# trico_embed01_atmpt02.net
KiCad netlist of a schematic drawn in EAGLE
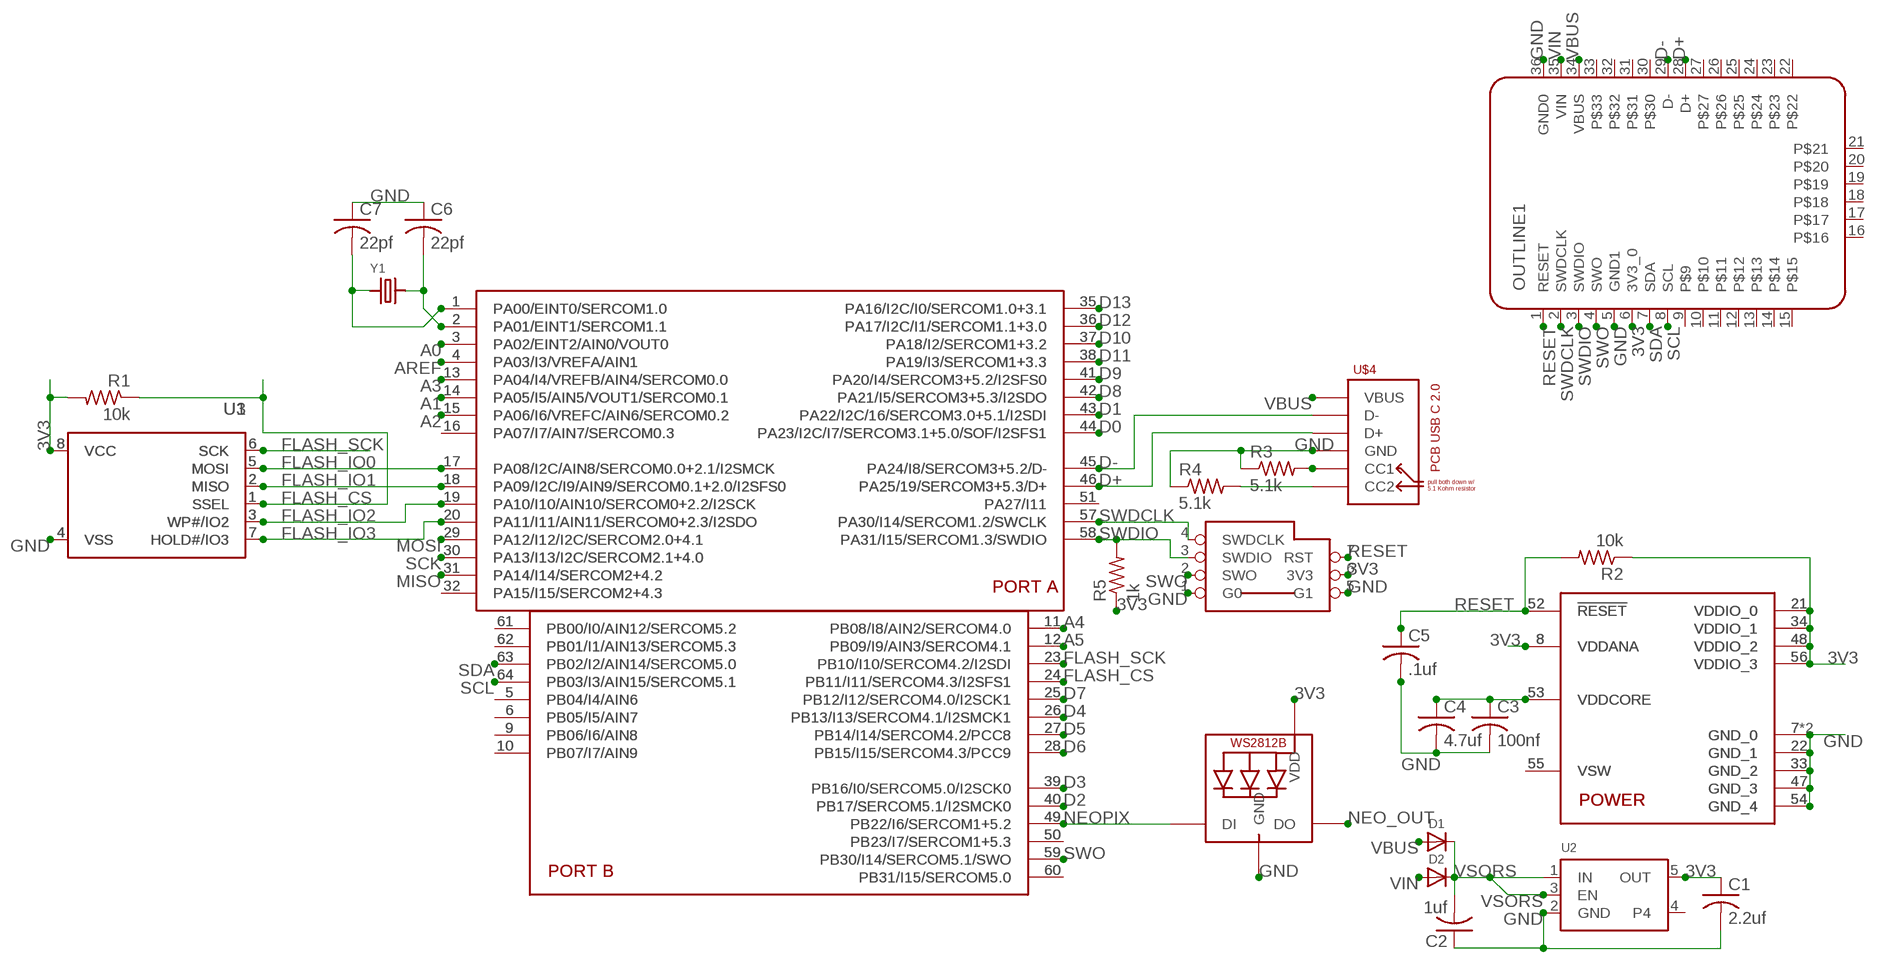
[diagram p0: schematic, sheet 1]

(export (version "E")
  (design (tool "Eeschema 10.0.6"))
  (components
    (comp (ref "C1")
      (value "2.2uf")
      (footprint "eagle-import:TG-C0805MP")
      (libsource (lib "eagle-import") (part "C-TG"))
    )
    (comp (ref "C2")
      (value "1uf")
      (footprint "eagle-import:TG-C0805MP")
      (libsource (lib "eagle-import") (part "C-TG"))
    )
    (comp (ref "C3")
      (value "100nf")
      (footprint "eagle-import:TG-C0805MP")
      (libsource (lib "eagle-import") (part "C-TG"))
    )
    (comp (ref "C4")
      (value "4.7uf")
      (footprint "eagle-import:TG-C0805MP")
      (libsource (lib "eagle-import") (part "C-TG"))
    )
    (comp (ref "C5")
      (value ".1uf")
      (footprint "eagle-import:TG-C0805MP")
      (libsource (lib "eagle-import") (part "C-TG"))
    )
    (comp (ref "C6")
      (value "22pf")
      (footprint "eagle-import:TG-C0805MP")
      (libsource (lib "eagle-import") (part "C-TG"))
    )
    (comp (ref "C7")
      (value "22pf")
      (footprint "eagle-import:TG-C0805MP")
      (libsource (lib "eagle-import") (part "C-TG"))
    )
    (comp (ref "D1")
      (value "DIODESOD-123")
      (footprint "eagle-import:SOD-123")
      (libsource (lib "eagle-import") (part "DIODESOD-123"))
    )
    (comp (ref "D2")
      (value "DIODESOD-123")
      (footprint "eagle-import:SOD-123")
      (libsource (lib "eagle-import") (part "DIODESOD-123"))
    )
    (comp (ref "LED1")
      (value "LED-NEO-WS2812B3535")
      (footprint "eagle-import:LED3535")
      (libsource (lib "eagle-import") (part "LED-NEO-WS2812B3535"))
    )
    (comp (ref "OUTLINE1")
      (value "TRIOC_DEV_36_EMBED_01BREAK_TPLC")
      (footprint "eagle-import:TRICO_DEV_01_BRK_TPLC_HYBRID")
      (libsource (lib "eagle-import") (part "TRIOC_DEV_36_EMBED_01BREAK_TPLC"))
    )
    (comp (ref "R1")
      (value "10k")
      (footprint "eagle-import:TG-R0805")
      (libsource (lib "eagle-import") (part "R_TG"))
    )
    (comp (ref "R2")
      (value "10k")
      (footprint "eagle-import:TG-R0805")
      (libsource (lib "eagle-import") (part "R_TG"))
    )
    (comp (ref "R3")
      (value "5.1k")
      (footprint "eagle-import:TG-R0805")
      (libsource (lib "eagle-import") (part "0TG-Lib v01.4_R_TG"))
    )
    (comp (ref "R4")
      (value "5.1k")
      (footprint "eagle-import:TG-R0805")
      (libsource (lib "eagle-import") (part "0TG-Lib v01.4_R_TG"))
    )
    (comp (ref "R5")
      (value "1k")
      (footprint "eagle-import:TG-R0805")
      (libsource (lib "eagle-import") (part "R_TG"))
    )
    (comp (ref "U$1")
      (value "MCU-ATSAMD51J-ADATQFP")
      (footprint "eagle-import:QFP50P1200X1200X120-64N")
      (libsource (lib "eagle-import") (part "MCU-ATSAMD51J-ADATQFP"))
    )
    (comp (ref "U$2")
      (value "MCU-ATSAMD51J-ADAADA")
      (footprint "eagle-import:MICROBUILDER_PQFN64-1")
      (libsource (lib "eagle-import") (part "0TG-Lib v01.4_MCU-ATSAMD51J-ADAADA"))
    )
    (comp (ref "U$3")
      (value "SWD_POGO")
      (footprint "eagle-import:SWD_POGO")
      (libsource (lib "eagle-import") (part "SWD_POGO"))
    )
    (comp (ref "U$4")
      (value "USB-C-PCB-USB-2.0-TYPE-CDS_2")
      (footprint "eagle-import:USB_TYPE_C_DS_2")
      (libsource (lib "eagle-import") (part "USB-C-PCB-USB-2.0-TYPE-CDS_2"))
    )
    (comp (ref "U1")
      (value "FLASH-SPI-SOIC8")
      (footprint "eagle-import:SOIC8_150MIL")
      (libsource (lib "eagle-import") (part "FLASH-SPI-SOIC8"))
    )
    (comp (ref "U2")
      (value "VREG_STD_MIN_SOT23-5")
      (footprint "eagle-import:SOT23-5")
      (libsource (lib "eagle-import") (part "VREG_STD_MIN_SOT23-5"))
    )
    (comp (ref "U3")
      (value "FLASH-SPI-SOIC8208MIL")
      (footprint "eagle-import:SOIC8_208MIL")
      (libsource (lib "eagle-import") (part "FLASH-SPI-SOIC8208MIL"))
    )
    (comp (ref "Y1")
      (value "XTAL_ADA4.9X1.8")
      (footprint "eagle-import:MICROBUILDER_CRYSTAL_4.9X1.8")
      (libsource (lib "eagle-import") (part "XTAL_ADA4.9X1.8"))
    )
  )
  (nets
    (net (code "1") (name "/3V3") (class "Default")
      (node (ref "C1") (pin "1") (pinfunction "1_1") (pintype "passive"))
      (node (ref "LED1") (pin "2") (pinfunction "VDD_2") (pintype "power_in"))
      (node (ref "OUTLINE1") (pin "6") (pinfunction "3V3_0_6") (pintype "bidirectional"))
      (node (ref "R1") (pin "2") (pinfunction "2_2") (pintype "passive"))
      (node (ref "R2") (pin "1") (pinfunction "1_1") (pintype "passive"))
      (node (ref "R5") (pin "1") (pinfunction "1_1") (pintype "passive"))
      (node (ref "U$1") (pin "21") (pinfunction "VDDIO_0_21") (pintype "bidirectional"))
      (node (ref "U$1") (pin "34") (pinfunction "VDDIO_1_34") (pintype "bidirectional"))
      (node (ref "U$1") (pin "48") (pinfunction "VDDIO_2_48") (pintype "bidirectional"))
      (node (ref "U$1") (pin "56") (pinfunction "VDDIO_3_56") (pintype "bidirectional"))
      (node (ref "U$1") (pin "8") (pinfunction "VDDANA_8") (pintype "bidirectional"))
      (node (ref "U$2") (pin "21") (pinfunction "VDDIO_0_21") (pintype "bidirectional"))
      (node (ref "U$2") (pin "34") (pinfunction "VDDIO_1_34") (pintype "bidirectional"))
      (node (ref "U$2") (pin "48") (pinfunction "VDDIO_2_48") (pintype "bidirectional"))
      (node (ref "U$2") (pin "56") (pinfunction "VDDIO_3_56") (pintype "bidirectional"))
      (node (ref "U$2") (pin "8") (pinfunction "VDDANA_8") (pintype "bidirectional"))
      (node (ref "U$3") (pin "6") (pinfunction "3V3_6") (pintype "bidirectional"))
      (node (ref "U1") (pin "8") (pinfunction "VCC_8") (pintype "bidirectional"))
      (node (ref "U2") (pin "5") (pinfunction "OUT_5") (pintype "power_in"))
      (node (ref "U3") (pin "8") (pinfunction "VCC_8") (pintype "bidirectional"))
    )
    (net (code "2") (name "/A0") (class "Default")
      (node (ref "U$1") (pin "3") (pinfunction "PA02/EINT2/AIN0/VOUT0_3") (pintype "bidirectional"))
      (node (ref "U$2") (pin "3") (pinfunction "PA02/EINT2/AIN0/VOUT0_3") (pintype "bidirectional"))
    )
    (net (code "3") (name "/A1") (class "Default")
      (node (ref "U$1") (pin "14") (pinfunction "PA05/I5/AIN5/VOUT1/SERCOM0.1_14") (pintype "bidirectional"))
      (node (ref "U$2") (pin "14") (pinfunction "PA05/I5/AIN5/VOUT1/SERCOM0.1_14") (pintype "bidirectional"))
    )
    (net (code "4") (name "/A2") (class "Default")
      (node (ref "U$1") (pin "15") (pinfunction "PA06/I6/VREFC/AIN6/SERCOM0.2_15") (pintype "bidirectional"))
      (node (ref "U$2") (pin "15") (pinfunction "PA06/I6/VREFC/AIN6/SERCOM0.2_15") (pintype "bidirectional"))
    )
    (net (code "5") (name "/A3") (class "Default")
      (node (ref "U$1") (pin "13") (pinfunction "PA04/I4/VREFB/AIN4/SERCOM0.0_13") (pintype "bidirectional"))
      (node (ref "U$2") (pin "13") (pinfunction "PA04/I4/VREFB/AIN4/SERCOM0.0_13") (pintype "bidirectional"))
    )
    (net (code "6") (name "/A4") (class "Default")
      (node (ref "U$1") (pin "11") (pinfunction "PB08/I8/AIN2/SERCOM4.0_11") (pintype "bidirectional"))
      (node (ref "U$2") (pin "11") (pinfunction "PB08/I8/AIN2/SERCOM4.0_11") (pintype "bidirectional"))
    )
    (net (code "7") (name "/A5") (class "Default")
      (node (ref "U$1") (pin "12") (pinfunction "PB09/I9/AIN3/SERCOM4.1_12") (pintype "bidirectional"))
      (node (ref "U$2") (pin "12") (pinfunction "PB09/I9/AIN3/SERCOM4.1_12") (pintype "bidirectional"))
    )
    (net (code "8") (name "/AREF") (class "Default")
      (node (ref "U$1") (pin "4") (pinfunction "PA03/I3/VREFA/AIN1_4") (pintype "bidirectional"))
      (node (ref "U$2") (pin "4") (pinfunction "PA03/I3/VREFA/AIN1_4") (pintype "bidirectional"))
    )
    (net (code "9") (name "/D+") (class "Default")
      (node (ref "OUTLINE1") (pin "28") (pinfunction "D+_28") (pintype "bidirectional"))
      (node (ref "U$1") (pin "46") (pinfunction "PA25/19/SERCOM3+5.3/D+_46") (pintype "bidirectional"))
      (node (ref "U$2") (pin "46") (pinfunction "PA25/19/SERCOM3+5.3/D+_46") (pintype "bidirectional"))
      (node (ref "U$4") (pin "A6") (pinfunction "D+_A6") (pintype "bidirectional"))
      (node (ref "U$4") (pin "B6") (pinfunction "D+_B6") (pintype "bidirectional"))
    )
    (net (code "10") (name "/D-") (class "Default")
      (node (ref "OUTLINE1") (pin "29") (pinfunction "D-_29") (pintype "bidirectional"))
      (node (ref "U$1") (pin "45") (pinfunction "PA24/I8/SERCOM3+5.2/D-_45") (pintype "bidirectional"))
      (node (ref "U$2") (pin "45") (pinfunction "PA24/I8/SERCOM3+5.2/D-_45") (pintype "bidirectional"))
      (node (ref "U$4") (pin "A7") (pinfunction "D-_A7") (pintype "bidirectional"))
      (node (ref "U$4") (pin "B7") (pinfunction "D-_B7") (pintype "bidirectional"))
    )
    (net (code "11") (name "/D0") (class "Default")
      (node (ref "U$1") (pin "44") (pinfunction "PA23/I2C/I7/SERCOM3.1+5.0/SOF/I2SFS1_44") (pintype "bidirectional"))
      (node (ref "U$2") (pin "44") (pinfunction "PA23/I2C/I7/SERCOM3.1+5.0/SOF/I2SFS1_44") (pintype "bidirectional"))
    )
    (net (code "12") (name "/D1") (class "Default")
      (node (ref "U$1") (pin "43") (pinfunction "PA22/I2C/16/SERCOM3.0+5.1/I2SDI_43") (pintype "bidirectional"))
      (node (ref "U$2") (pin "43") (pinfunction "PA22/I2C/16/SERCOM3.0+5.1/I2SDI_43") (pintype "bidirectional"))
    )
    (net (code "13") (name "/D2") (class "Default")
      (node (ref "U$1") (pin "40") (pinfunction "PB17/SERCOM5.1/I2SMCK0_40") (pintype "bidirectional"))
      (node (ref "U$2") (pin "40") (pinfunction "PB17/SERCOM5.1/I2SMCK0_40") (pintype "bidirectional"))
    )
    (net (code "14") (name "/D3") (class "Default")
      (node (ref "U$1") (pin "39") (pinfunction "PB16/I0/SERCOM5.0/I2SCK0_39") (pintype "bidirectional"))
      (node (ref "U$2") (pin "39") (pinfunction "PB16/I0/SERCOM5.0/I2SCK0_39") (pintype "bidirectional"))
    )
    (net (code "15") (name "/D4") (class "Default")
      (node (ref "U$1") (pin "26") (pinfunction "PB13/I13/SERCOM4.1/I2SMCK1_26") (pintype "bidirectional"))
      (node (ref "U$2") (pin "26") (pinfunction "PB13/I13/SERCOM4.1/I2SMCK1_26") (pintype "bidirectional"))
    )
    (net (code "16") (name "/D5") (class "Default")
      (node (ref "U$1") (pin "27") (pinfunction "PB14/I14/SERCOM4.2/PCC8_27") (pintype "bidirectional"))
      (node (ref "U$2") (pin "27") (pinfunction "PB14/I14/SERCOM4.2/PCC8_27") (pintype "bidirectional"))
    )
    (net (code "17") (name "/D6") (class "Default")
      (node (ref "U$1") (pin "28") (pinfunction "PB15/I15/SERCOM4.3/PCC9_28") (pintype "bidirectional"))
      (node (ref "U$2") (pin "28") (pinfunction "PB15/I15/SERCOM4.3/PCC9_28") (pintype "bidirectional"))
    )
    (net (code "18") (name "/D7") (class "Default")
      (node (ref "U$1") (pin "25") (pinfunction "PB12/I12/SERCOM4.0/I2SCK1_25") (pintype "bidirectional"))
      (node (ref "U$2") (pin "25") (pinfunction "PB12/I12/SERCOM4.0/I2SCK1_25") (pintype "bidirectional"))
    )
    (net (code "19") (name "/D8") (class "Default")
      (node (ref "U$1") (pin "42") (pinfunction "PA21/I5/SERCOM3+5.3/I2SDO_42") (pintype "bidirectional"))
      (node (ref "U$2") (pin "42") (pinfunction "PA21/I5/SERCOM3+5.3/I2SDO_42") (pintype "bidirectional"))
    )
    (net (code "20") (name "/D9") (class "Default")
      (node (ref "U$1") (pin "41") (pinfunction "PA20/I4/SERCOM3+5.2/I2SFS0_41") (pintype "bidirectional"))
      (node (ref "U$2") (pin "41") (pinfunction "PA20/I4/SERCOM3+5.2/I2SFS0_41") (pintype "bidirectional"))
    )
    (net (code "21") (name "/D10") (class "Default")
      (node (ref "U$1") (pin "37") (pinfunction "PA18/I2/SERCOM1+3.2_37") (pintype "bidirectional"))
      (node (ref "U$2") (pin "37") (pinfunction "PA18/I2/SERCOM1+3.2_37") (pintype "bidirectional"))
    )
    (net (code "22") (name "/D11") (class "Default")
      (node (ref "U$1") (pin "38") (pinfunction "PA19/I3/SERCOM1+3.3_38") (pintype "bidirectional"))
      (node (ref "U$2") (pin "38") (pinfunction "PA19/I3/SERCOM1+3.3_38") (pintype "bidirectional"))
    )
    (net (code "23") (name "/D12") (class "Default")
      (node (ref "U$1") (pin "36") (pinfunction "PA17/I2C/I1/SERCOM1.1+3.0_36") (pintype "bidirectional"))
      (node (ref "U$2") (pin "36") (pinfunction "PA17/I2C/I1/SERCOM1.1+3.0_36") (pintype "bidirectional"))
    )
    (net (code "24") (name "/D13") (class "Default")
      (node (ref "U$1") (pin "35") (pinfunction "PA16/I2C/I0/SERCOM1.0+3.1_35") (pintype "bidirectional"))
      (node (ref "U$2") (pin "35") (pinfunction "PA16/I2C/I0/SERCOM1.0+3.1_35") (pintype "bidirectional"))
    )
    (net (code "25") (name "/FLASH_CS") (class "Default")
      (node (ref "R1") (pin "1") (pinfunction "1_1") (pintype "passive"))
      (node (ref "U$1") (pin "24") (pinfunction "PB11/I11/SERCOM4.3/I2SFS1_24") (pintype "bidirectional"))
      (node (ref "U$2") (pin "24") (pinfunction "PB11/I11/SERCOM4.3/I2SFS1_24") (pintype "bidirectional"))
      (node (ref "U1") (pin "1") (pinfunction "SSEL_1") (pintype "bidirectional"))
      (node (ref "U3") (pin "1") (pinfunction "SSEL_1") (pintype "bidirectional"))
    )
    (net (code "26") (name "/FLASH_IO0") (class "Default")
      (node (ref "U$1") (pin "17") (pinfunction "PA08/I2C/AIN8/SERCOM0.0+2.1/I2SMCK_17") (pintype "bidirectional"))
      (node (ref "U$2") (pin "17") (pinfunction "PA08/I2C/AIN8/SERCOM0.0+2.1/I2SMCK_17") (pintype "bidirectional"))
      (node (ref "U1") (pin "5") (pinfunction "MOSI_5") (pintype "bidirectional"))
      (node (ref "U3") (pin "5") (pinfunction "MOSI_5") (pintype "bidirectional"))
    )
    (net (code "27") (name "/FLASH_IO1") (class "Default")
      (node (ref "U$1") (pin "18") (pinfunction "PA09/I2C/I9/AIN9/SERCOM0.1+2.0/I2SFS0_18") (pintype "bidirectional"))
      (node (ref "U$2") (pin "18") (pinfunction "PA09/I2C/I9/AIN9/SERCOM0.1+2.0/I2SFS0_18") (pintype "bidirectional"))
      (node (ref "U1") (pin "2") (pinfunction "MISO_2") (pintype "bidirectional"))
      (node (ref "U3") (pin "2") (pinfunction "MISO_2") (pintype "bidirectional"))
    )
    (net (code "28") (name "/FLASH_IO2") (class "Default")
      (node (ref "U$1") (pin "19") (pinfunction "PA10/I10/AIN10/SERCOM0+2.2/I2SCK_19") (pintype "bidirectional"))
      (node (ref "U$2") (pin "19") (pinfunction "PA10/I10/AIN10/SERCOM0+2.2/I2SCK_19") (pintype "bidirectional"))
      (node (ref "U1") (pin "3") (pinfunction "WP#/IO2_3") (pintype "bidirectional"))
      (node (ref "U3") (pin "3") (pinfunction "WP#/IO2_3") (pintype "bidirectional"))
    )
    (net (code "29") (name "/FLASH_IO3") (class "Default")
      (node (ref "U$1") (pin "20") (pinfunction "PA11/I11/AIN11/SERCOM0+2.3/I2SDO_20") (pintype "bidirectional"))
      (node (ref "U$2") (pin "20") (pinfunction "PA11/I11/AIN11/SERCOM0+2.3/I2SDO_20") (pintype "bidirectional"))
      (node (ref "U1") (pin "7") (pinfunction "HOLD#/IO3_7") (pintype "bidirectional"))
      (node (ref "U3") (pin "7") (pinfunction "HOLD#/IO3_7") (pintype "bidirectional"))
    )
    (net (code "30") (name "/FLASH_SCK") (class "Default")
      (node (ref "U$1") (pin "23") (pinfunction "PB10/I10/SERCOM4.2/I2SDI_23") (pintype "bidirectional"))
      (node (ref "U$2") (pin "23") (pinfunction "PB10/I10/SERCOM4.2/I2SDI_23") (pintype "bidirectional"))
      (node (ref "U1") (pin "6") (pinfunction "SCK_6") (pintype "bidirectional"))
      (node (ref "U3") (pin "6") (pinfunction "SCK_6") (pintype "bidirectional"))
    )
    (net (code "31") (name "/GND") (class "Default")
      (node (ref "C1") (pin "2") (pinfunction "2_2") (pintype "passive"))
      (node (ref "C2") (pin "1") (pinfunction "1_1") (pintype "passive"))
      (node (ref "C3") (pin "2") (pinfunction "2_2") (pintype "passive"))
      (node (ref "C4") (pin "2") (pinfunction "2_2") (pintype "passive"))
      (node (ref "C5") (pin "2") (pinfunction "2_2") (pintype "passive"))
      (node (ref "C6") (pin "1") (pinfunction "1_1") (pintype "passive"))
      (node (ref "C7") (pin "1") (pinfunction "1_1") (pintype "passive"))
      (node (ref "LED1") (pin "4") (pinfunction "GND_4") (pintype "power_in"))
      (node (ref "OUTLINE1") (pin "36") (pinfunction "GND0_36") (pintype "bidirectional"))
      (node (ref "OUTLINE1") (pin "5") (pinfunction "GND1_5") (pintype "bidirectional"))
      (node (ref "R3") (pin "1") (pinfunction "1_1") (pintype "passive"))
      (node (ref "R4") (pin "1") (pinfunction "1_1") (pintype "passive"))
      (node (ref "U$1") (pin "22") (pinfunction "GND_1_22") (pintype "bidirectional"))
      (node (ref "U$1") (pin "33") (pinfunction "GND_2_33") (pintype "bidirectional"))
      (node (ref "U$1") (pin "47") (pinfunction "GND_3_47") (pintype "bidirectional"))
      (node (ref "U$1") (pin "54") (pinfunction "GND_4_54") (pintype "bidirectional"))
      (node (ref "U$1") (pin "7") (pinfunction "GND_0_7") (pintype "bidirectional"))
      (node (ref "U$2") (pin "22") (pinfunction "GND_1_22") (pintype "bidirectional"))
      (node (ref "U$2") (pin "33") (pinfunction "GND_2_33") (pintype "bidirectional"))
      (node (ref "U$2") (pin "47") (pinfunction "GND_3_47") (pintype "bidirectional"))
      (node (ref "U$2") (pin "54") (pinfunction "GND_4_54") (pintype "bidirectional"))
      (node (ref "U$2") (pin "7") (pinfunction "GND_0_7") (pintype "bidirectional"))
      (node (ref "U$2") (pin "EXP") (pinfunction "GND_0_EXP") (pintype "bidirectional"))
      (node (ref "U$3") (pin "1") (pinfunction "G0_1") (pintype "bidirectional"))
      (node (ref "U$3") (pin "5") (pinfunction "G1_5") (pintype "bidirectional"))
      (node (ref "U$4") (pin "A1") (pinfunction "GND_A1") (pintype "bidirectional"))
      (node (ref "U$4") (pin "A12") (pinfunction "GND_A12") (pintype "bidirectional"))
      (node (ref "U$4") (pin "B1") (pinfunction "GND_B1") (pintype "bidirectional"))
      (node (ref "U$4") (pin "B12") (pinfunction "GND_B12") (pintype "bidirectional"))
      (node (ref "U1") (pin "4") (pinfunction "VSS_4") (pintype "bidirectional"))
      (node (ref "U2") (pin "2") (pinfunction "GND_2") (pintype "power_in"))
      (node (ref "U3") (pin "4") (pinfunction "VSS_4") (pintype "bidirectional"))
    )
    (net (code "32") (name "/MISO") (class "Default")
      (node (ref "U$1") (pin "31") (pinfunction "PA14/I14/SERCOM2+4.2_31") (pintype "bidirectional"))
      (node (ref "U$2") (pin "31") (pinfunction "PA14/I14/SERCOM2+4.2_31") (pintype "bidirectional"))
    )
    (net (code "33") (name "/MOSI") (class "Default")
      (node (ref "U$1") (pin "29") (pinfunction "PA12/I12/I2C/SERCOM2.0+4.1_29") (pintype "bidirectional"))
      (node (ref "U$2") (pin "29") (pinfunction "PA12/I12/I2C/SERCOM2.0+4.1_29") (pintype "bidirectional"))
    )
    (net (code "34") (name "/NEOPIX") (class "Default")
      (node (ref "LED1") (pin "1") (pinfunction "DI_1") (pintype "input"))
      (node (ref "U$1") (pin "49") (pinfunction "PB22/I6/SERCOM1+5.2_49") (pintype "bidirectional"))
      (node (ref "U$2") (pin "49") (pinfunction "PB22/I6/SERCOM1+5.2_49") (pintype "bidirectional"))
    )
    (net (code "35") (name "/NEO_OUT") (class "Default")
      (node (ref "LED1") (pin "3") (pinfunction "DO_3") (pintype "output"))
    )
    (net (code "36") (name "/RESET") (class "Default")
      (node (ref "C5") (pin "1") (pinfunction "1_1") (pintype "passive"))
      (node (ref "OUTLINE1") (pin "1") (pinfunction "RESET_1") (pintype "bidirectional"))
      (node (ref "R2") (pin "2") (pinfunction "2_2") (pintype "passive"))
      (node (ref "U$1") (pin "52") (pinfunction "~{RESET}_52") (pintype "bidirectional"))
      (node (ref "U$2") (pin "52") (pinfunction "~{RESET}_52") (pintype "bidirectional"))
      (node (ref "U$3") (pin "7") (pinfunction "RST_7") (pintype "bidirectional"))
    )
    (net (code "37") (name "/SCK") (class "Default")
      (node (ref "U$1") (pin "30") (pinfunction "PA13/I13/I2C/SERCOM2.1+4.0_30") (pintype "bidirectional"))
      (node (ref "U$2") (pin "30") (pinfunction "PA13/I13/I2C/SERCOM2.1+4.0_30") (pintype "bidirectional"))
    )
    (net (code "38") (name "/SCL") (class "Default")
      (node (ref "OUTLINE1") (pin "8") (pinfunction "SCL_8") (pintype "bidirectional"))
      (node (ref "U$1") (pin "64") (pinfunction "PB03/I3/AIN15/SERCOM5.1_64") (pintype "bidirectional"))
      (node (ref "U$2") (pin "64") (pinfunction "PB03/I3/AIN15/SERCOM5.1_64") (pintype "bidirectional"))
    )
    (net (code "39") (name "/SDA") (class "Default")
      (node (ref "OUTLINE1") (pin "7") (pinfunction "SDA_7") (pintype "bidirectional"))
      (node (ref "U$1") (pin "63") (pinfunction "PB02/I2/AIN14/SERCOM5.0_63") (pintype "bidirectional"))
      (node (ref "U$2") (pin "63") (pinfunction "PB02/I2/AIN14/SERCOM5.0_63") (pintype "bidirectional"))
    )
    (net (code "40") (name "/SWDCLK") (class "Default")
      (node (ref "OUTLINE1") (pin "2") (pinfunction "SWDCLK_2") (pintype "bidirectional"))
      (node (ref "U$1") (pin "57") (pinfunction "PA30/I14/SERCOM1.2/SWCLK_57") (pintype "bidirectional"))
      (node (ref "U$2") (pin "57") (pinfunction "PA30/I14/SERCOM1.2/SWCLK_57") (pintype "bidirectional"))
      (node (ref "U$3") (pin "4") (pinfunction "SWDCLK_4") (pintype "bidirectional"))
    )
    (net (code "41") (name "/SWDIO") (class "Default")
      (node (ref "OUTLINE1") (pin "3") (pinfunction "SWDIO_3") (pintype "bidirectional"))
      (node (ref "R5") (pin "2") (pinfunction "2_2") (pintype "passive"))
      (node (ref "U$1") (pin "58") (pinfunction "PA31/I15/SERCOM1.3/SWDIO_58") (pintype "bidirectional"))
      (node (ref "U$2") (pin "58") (pinfunction "PA31/I15/SERCOM1.3/SWDIO_58") (pintype "bidirectional"))
      (node (ref "U$3") (pin "3") (pinfunction "SWDIO_3") (pintype "bidirectional"))
    )
    (net (code "42") (name "/SWO") (class "Default")
      (node (ref "OUTLINE1") (pin "4") (pinfunction "SWO_4") (pintype "bidirectional"))
      (node (ref "U$1") (pin "59") (pinfunction "PB30/I14/SERCOM5.1/SWO_59") (pintype "bidirectional"))
      (node (ref "U$2") (pin "59") (pinfunction "PB30/I14/SERCOM5.1/SWO_59") (pintype "bidirectional"))
      (node (ref "U$3") (pin "2") (pinfunction "SWO_2") (pintype "bidirectional"))
    )
    (net (code "43") (name "/VBUS") (class "Default")
      (node (ref "D1") (pin "A") (pinfunction "A_A") (pintype "passive"))
      (node (ref "OUTLINE1") (pin "34") (pinfunction "VBUS_34") (pintype "bidirectional"))
      (node (ref "U$4") (pin "A4") (pinfunction "VBUS_A4") (pintype "bidirectional"))
      (node (ref "U$4") (pin "A9") (pinfunction "VBUS_A9") (pintype "bidirectional"))
      (node (ref "U$4") (pin "B4") (pinfunction "VBUS_B4") (pintype "bidirectional"))
      (node (ref "U$4") (pin "B9") (pinfunction "VBUS_B9") (pintype "bidirectional"))
    )
    (net (code "44") (name "/VIN") (class "Default")
      (node (ref "D2") (pin "A") (pinfunction "A_A") (pintype "passive"))
      (node (ref "OUTLINE1") (pin "35") (pinfunction "VIN_35") (pintype "bidirectional"))
    )
    (net (code "45") (name "/VSORS") (class "Default")
      (node (ref "C2") (pin "2") (pinfunction "2_2") (pintype "passive"))
      (node (ref "D1") (pin "C") (pinfunction "C_C") (pintype "passive"))
      (node (ref "D2") (pin "C") (pinfunction "C_C") (pintype "passive"))
      (node (ref "U2") (pin "1") (pinfunction "IN_1") (pintype "power_in"))
      (node (ref "U2") (pin "3") (pinfunction "EN_3") (pintype "input"))
    )
    (net (code "46") (name "Net-(U$1A-PA00{slash}EINT0{slash}SERCOM1.0)") (class "Default")
      (node (ref "C7") (pin "2") (pinfunction "2_2") (pintype "passive"))
      (node (ref "U$1") (pin "1") (pinfunction "PA00/EINT0/SERCOM1.0_1") (pintype "bidirectional"))
      (node (ref "U$2") (pin "1") (pinfunction "PA00/EINT0/SERCOM1.0_1") (pintype "bidirectional"))
      (node (ref "Y1") (pin "1") (pinfunction "1_1") (pintype "passive"))
    )
    (net (code "47") (name "Net-(U$1A-PA01{slash}EINT1{slash}SERCOM1.1)") (class "Default")
      (node (ref "C6") (pin "2") (pinfunction "2_2") (pintype "passive"))
      (node (ref "U$1") (pin "2") (pinfunction "PA01/EINT1/SERCOM1.1_2") (pintype "bidirectional"))
      (node (ref "U$2") (pin "2") (pinfunction "PA01/EINT1/SERCOM1.1_2") (pintype "bidirectional"))
      (node (ref "Y1") (pin "2") (pinfunction "2_2") (pintype "passive"))
    )
    (net (code "48") (name "Net-(U$1A-PA07{slash}I7{slash}AIN7{slash}SERCOM0.3)") (class "Default")
      (node (ref "U$1") (pin "16") (pinfunction "PA07/I7/AIN7/SERCOM0.3_16") (pintype "bidirectional"))
      (node (ref "U$2") (pin "16") (pinfunction "PA07/I7/AIN7/SERCOM0.3_16") (pintype "bidirectional"))
    )
    (net (code "49") (name "Net-(U$1A-PA15{slash}I15{slash}SERCOM2+4.3)") (class "Default")
      (node (ref "U$1") (pin "32") (pinfunction "PA15/I15/SERCOM2+4.3_32") (pintype "bidirectional"))
      (node (ref "U$2") (pin "32") (pinfunction "PA15/I15/SERCOM2+4.3_32") (pintype "bidirectional"))
    )
    (net (code "50") (name "Net-(U$1A-PA27{slash}I11)") (class "Default")
      (node (ref "U$1") (pin "51") (pinfunction "PA27/I11_51") (pintype "bidirectional"))
      (node (ref "U$2") (pin "51") (pinfunction "PA27/I11_51") (pintype "bidirectional"))
    )
    (net (code "51") (name "Net-(U$1B-PB00{slash}I0{slash}AIN12{slash}SERCOM5.2)") (class "Default")
      (node (ref "U$1") (pin "61") (pinfunction "PB00/I0/AIN12/SERCOM5.2_61") (pintype "bidirectional"))
      (node (ref "U$2") (pin "61") (pinfunction "PB00/I0/AIN12/SERCOM5.2_61") (pintype "bidirectional"))
    )
    (net (code "52") (name "Net-(U$1B-PB01{slash}I1{slash}AIN13{slash}SERCOM5.3)") (class "Default")
      (node (ref "U$1") (pin "62") (pinfunction "PB01/I1/AIN13/SERCOM5.3_62") (pintype "bidirectional"))
      (node (ref "U$2") (pin "62") (pinfunction "PB01/I1/AIN13/SERCOM5.3_62") (pintype "bidirectional"))
    )
    (net (code "53") (name "Net-(U$1B-PB04{slash}I4{slash}AIN6)") (class "Default")
      (node (ref "U$1") (pin "5") (pinfunction "PB04/I4/AIN6_5") (pintype "bidirectional"))
      (node (ref "U$2") (pin "5") (pinfunction "PB04/I4/AIN6_5") (pintype "bidirectional"))
    )
    (net (code "54") (name "Net-(U$1B-PB05{slash}I5{slash}AIN7)") (class "Default")
      (node (ref "U$1") (pin "6") (pinfunction "PB05/I5/AIN7_6") (pintype "bidirectional"))
      (node (ref "U$2") (pin "6") (pinfunction "PB05/I5/AIN7_6") (pintype "bidirectional"))
    )
    (net (code "55") (name "Net-(U$1B-PB06{slash}I6{slash}AIN8)") (class "Default")
      (node (ref "U$1") (pin "9") (pinfunction "PB06/I6/AIN8_9") (pintype "bidirectional"))
      (node (ref "U$2") (pin "9") (pinfunction "PB06/I6/AIN8_9") (pintype "bidirectional"))
    )
    (net (code "56") (name "Net-(U$1B-PB07{slash}I7{slash}AIN9)") (class "Default")
      (node (ref "U$1") (pin "10") (pinfunction "PB07/I7/AIN9_10") (pintype "bidirectional"))
      (node (ref "U$2") (pin "10") (pinfunction "PB07/I7/AIN9_10") (pintype "bidirectional"))
    )
    (net (code "57") (name "Net-(U$1B-PB23{slash}I7{slash}SERCOM1+5.3)") (class "Default")
      (node (ref "U$1") (pin "50") (pinfunction "PB23/I7/SERCOM1+5.3_50") (pintype "bidirectional"))
      (node (ref "U$2") (pin "50") (pinfunction "PB23/I7/SERCOM1+5.3_50") (pintype "bidirectional"))
    )
    (net (code "58") (name "Net-(U$1B-PB31{slash}I15{slash}SERCOM5.0)") (class "Default")
      (node (ref "U$1") (pin "60") (pinfunction "PB31/I15/SERCOM5.0_60") (pintype "bidirectional"))
      (node (ref "U$2") (pin "60") (pinfunction "PB31/I15/SERCOM5.0_60") (pintype "bidirectional"))
    )
    (net (code "59") (name "Net-(U$1C-VDDCORE)") (class "Default")
      (node (ref "C3") (pin "1") (pinfunction "1_1") (pintype "passive"))
      (node (ref "C4") (pin "1") (pinfunction "1_1") (pintype "passive"))
      (node (ref "U$1") (pin "53") (pinfunction "VDDCORE_53") (pintype "bidirectional"))
      (node (ref "U$2") (pin "53") (pinfunction "VDDCORE_53") (pintype "bidirectional"))
    )
    (net (code "60") (name "Net-(U$1C-VSW)") (class "Default")
      (node (ref "U$1") (pin "55") (pinfunction "VSW_55") (pintype "bidirectional"))
      (node (ref "U$2") (pin "55") (pinfunction "VSW_55") (pintype "bidirectional"))
    )
    (net (code "61") (name "Net-(U$4-CC1)") (class "Default")
      (node (ref "R3") (pin "2") (pinfunction "2_2") (pintype "passive"))
      (node (ref "U$4") (pin "A5") (pinfunction "CC1_A5") (pintype "bidirectional"))
    )
    (net (code "62") (name "Net-(U$4-CC2)") (class "Default")
      (node (ref "R4") (pin "2") (pinfunction "2_2") (pintype "passive"))
      (node (ref "U$4") (pin "B5") (pinfunction "CC2_B5") (pintype "bidirectional"))
    )
    (net (code "63") (name "unconnected-(OUTLINE1-P$9-Pad9)") (class "Default")
      (node (ref "OUTLINE1") (pin "9") (pinfunction "P$9_9") (pintype "bidirectional"))
    )
    (net (code "64") (name "unconnected-(OUTLINE1-P$10-Pad10)") (class "Default")
      (node (ref "OUTLINE1") (pin "10") (pinfunction "P$10_10") (pintype "bidirectional"))
    )
    (net (code "65") (name "unconnected-(OUTLINE1-P$11-Pad11)") (class "Default")
      (node (ref "OUTLINE1") (pin "11") (pinfunction "P$11_11") (pintype "bidirectional"))
    )
    (net (code "66") (name "unconnected-(OUTLINE1-P$12-Pad12)") (class "Default")
      (node (ref "OUTLINE1") (pin "12") (pinfunction "P$12_12") (pintype "bidirectional"))
    )
    (net (code "67") (name "unconnected-(OUTLINE1-P$13-Pad13)") (class "Default")
      (node (ref "OUTLINE1") (pin "13") (pinfunction "P$13_13") (pintype "bidirectional"))
    )
    (net (code "68") (name "unconnected-(OUTLINE1-P$14-Pad14)") (class "Default")
      (node (ref "OUTLINE1") (pin "14") (pinfunction "P$14_14") (pintype "bidirectional"))
    )
    (net (code "69") (name "unconnected-(OUTLINE1-P$15-Pad15)") (class "Default")
      (node (ref "OUTLINE1") (pin "15") (pinfunction "P$15_15") (pintype "bidirectional"))
    )
    (net (code "70") (name "unconnected-(OUTLINE1-P$16-Pad16)") (class "Default")
      (node (ref "OUTLINE1") (pin "16") (pinfunction "P$16_16") (pintype "bidirectional"))
    )
    (net (code "71") (name "unconnected-(OUTLINE1-P$17-Pad17)") (class "Default")
      (node (ref "OUTLINE1") (pin "17") (pinfunction "P$17_17") (pintype "bidirectional"))
    )
    (net (code "72") (name "unconnected-(OUTLINE1-P$18-Pad18)") (class "Default")
      (node (ref "OUTLINE1") (pin "18") (pinfunction "P$18_18") (pintype "bidirectional"))
    )
    (net (code "73") (name "unconnected-(OUTLINE1-P$19-Pad19)") (class "Default")
      (node (ref "OUTLINE1") (pin "19") (pinfunction "P$19_19") (pintype "bidirectional"))
    )
    (net (code "74") (name "unconnected-(OUTLINE1-P$20-Pad20)") (class "Default")
      (node (ref "OUTLINE1") (pin "20") (pinfunction "P$20_20") (pintype "bidirectional"))
    )
    (net (code "75") (name "unconnected-(OUTLINE1-P$21-Pad21)") (class "Default")
      (node (ref "OUTLINE1") (pin "21") (pinfunction "P$21_21") (pintype "bidirectional"))
    )
    (net (code "76") (name "unconnected-(OUTLINE1-P$22-Pad22)") (class "Default")
      (node (ref "OUTLINE1") (pin "22") (pinfunction "P$22_22") (pintype "bidirectional"))
    )
    (net (code "77") (name "unconnected-(OUTLINE1-P$23-Pad23)") (class "Default")
      (node (ref "OUTLINE1") (pin "23") (pinfunction "P$23_23") (pintype "bidirectional"))
    )
    (net (code "78") (name "unconnected-(OUTLINE1-P$24-Pad24)") (class "Default")
      (node (ref "OUTLINE1") (pin "24") (pinfunction "P$24_24") (pintype "bidirectional"))
    )
    (net (code "79") (name "unconnected-(OUTLINE1-P$25-Pad25)") (class "Default")
      (node (ref "OUTLINE1") (pin "25") (pinfunction "P$25_25") (pintype "bidirectional"))
    )
    (net (code "80") (name "unconnected-(OUTLINE1-P$26-Pad26)") (class "Default")
      (node (ref "OUTLINE1") (pin "26") (pinfunction "P$26_26") (pintype "bidirectional"))
    )
    (net (code "81") (name "unconnected-(OUTLINE1-P$27-Pad27)") (class "Default")
      (node (ref "OUTLINE1") (pin "27") (pinfunction "P$27_27") (pintype "bidirectional"))
    )
    (net (code "82") (name "unconnected-(OUTLINE1-P$30-Pad30)") (class "Default")
      (node (ref "OUTLINE1") (pin "30") (pinfunction "P$30_30") (pintype "bidirectional"))
    )
    (net (code "83") (name "unconnected-(OUTLINE1-P$31-Pad31)") (class "Default")
      (node (ref "OUTLINE1") (pin "31") (pinfunction "P$31_31") (pintype "bidirectional"))
    )
    (net (code "84") (name "unconnected-(OUTLINE1-P$32-Pad32)") (class "Default")
      (node (ref "OUTLINE1") (pin "32") (pinfunction "P$32_32") (pintype "bidirectional"))
    )
    (net (code "85") (name "unconnected-(OUTLINE1-P$33-Pad33)") (class "Default")
      (node (ref "OUTLINE1") (pin "33") (pinfunction "P$33_33") (pintype "bidirectional"))
    )
    (net (code "86") (name "unconnected-(U2-P4-Pad4)") (class "Default")
      (node (ref "U2") (pin "4") (pinfunction "P4_4") (pintype "bidirectional"))
    )
  )
)
